# TB_Controller.net
KiCad netlist of a schematic drawn in Altium Designer
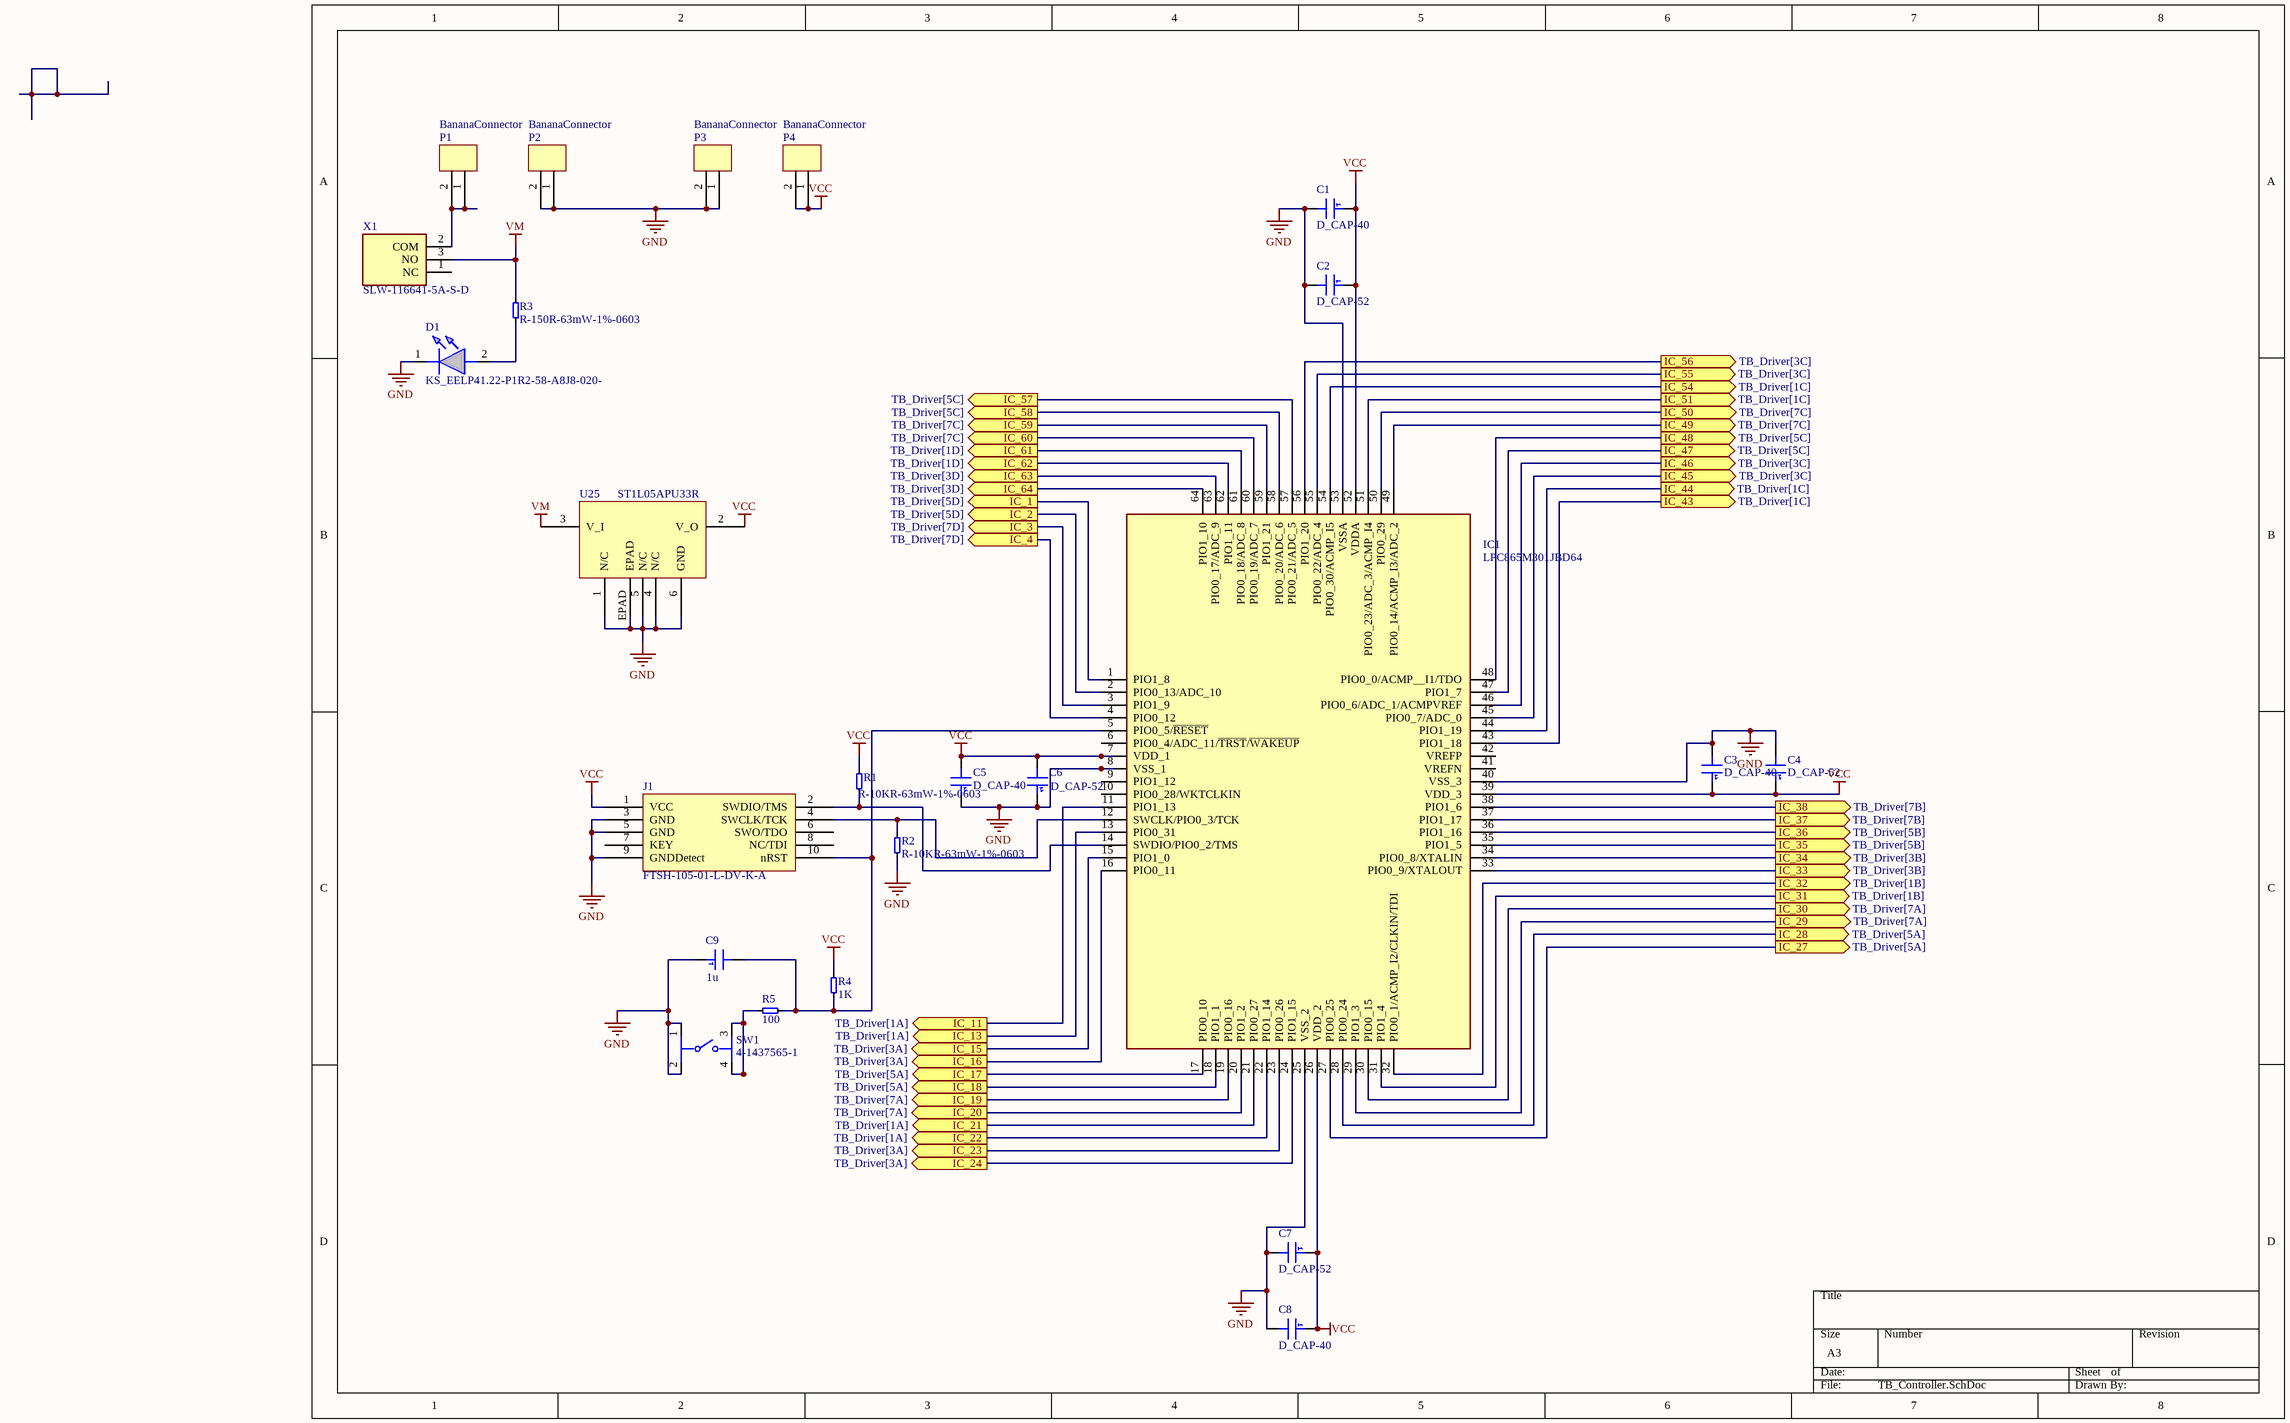
[diagram p0: TB_Controller.SchDoc]

(export (version "E")
  (design (tool "Eeschema 10.0.6"))
  (components
    (comp (ref "C1")
      (value "D_CAP-40")
      (footprint "CAP_0603H0.8")
      (description "Boite Labo 0603: Ceramic Cap, 10nF, 5%, 50V, CAP_0603H0.8")
      (fields (field (name "MANUFACTURER") "Murata") (field (name "DESIGNER") "R.Mastrocola"))
      (libsource (lib "A365 Rehosted HEPIA Vault") (part "Cap"))
    )
    (comp (ref "C2")
      (value "D_CAP-52")
      (footprint "CAP_0603H0.8")
      (description "Boite Labo 0603: Ceramic Cap, 100nF, 10%, 50V, CAP_0603H0.8")
      (fields (field (name "MANUFACTURER") "Murata") (field (name "DESIGNER") "R.Mastrocola"))
      (libsource (lib "A365 Rehosted HEPIA Vault") (part "Cap"))
    )
    (comp (ref "C3")
      (value "D_CAP-40")
      (footprint "CAP_0603H0.8")
      (description "Boite Labo 0603: Ceramic Cap, 10nF, 5%, 50V, CAP_0603H0.8")
      (fields (field (name "MANUFACTURER") "Murata") (field (name "DESIGNER") "R.Mastrocola"))
      (libsource (lib "A365 Rehosted HEPIA Vault") (part "Cap"))
    )
    (comp (ref "C4")
      (value "D_CAP-52")
      (footprint "CAP_0603H0.8")
      (description "Boite Labo 0603: Ceramic Cap, 100nF, 10%, 50V, CAP_0603H0.8")
      (fields (field (name "MANUFACTURER") "Murata") (field (name "DESIGNER") "R.Mastrocola"))
      (libsource (lib "A365 Rehosted HEPIA Vault") (part "Cap"))
    )
    (comp (ref "C5")
      (value "D_CAP-40")
      (footprint "CAP_0603H0.8")
      (description "Boite Labo 0603: Ceramic Cap, 10nF, 5%, 50V, CAP_0603H0.8")
      (fields (field (name "MANUFACTURER") "Murata") (field (name "DESIGNER") "R.Mastrocola"))
      (libsource (lib "A365 Rehosted HEPIA Vault") (part "Cap"))
    )
    (comp (ref "C6")
      (value "D_CAP-52")
      (footprint "CAP_0603H0.8")
      (description "Boite Labo 0603: Ceramic Cap, 100nF, 10%, 50V, CAP_0603H0.8")
      (fields (field (name "MANUFACTURER") "Murata") (field (name "DESIGNER") "R.Mastrocola"))
      (libsource (lib "A365 Rehosted HEPIA Vault") (part "Cap"))
    )
    (comp (ref "C7")
      (value "D_CAP-52")
      (footprint "CAP_0603H0.8")
      (description "Boite Labo 0603: Ceramic Cap, 100nF, 10%, 50V, CAP_0603H0.8")
      (fields (field (name "MANUFACTURER") "Murata") (field (name "DESIGNER") "R.Mastrocola"))
      (libsource (lib "A365 Rehosted HEPIA Vault") (part "Cap"))
    )
    (comp (ref "C8")
      (value "D_CAP-40")
      (footprint "CAP_0603H0.8")
      (description "Boite Labo 0603: Ceramic Cap, 10nF, 5%, 50V, CAP_0603H0.8")
      (fields (field (name "MANUFACTURER") "Murata") (field (name "DESIGNER") "R.Mastrocola"))
      (libsource (lib "A365 Rehosted HEPIA Vault") (part "Cap"))
    )
    (comp (ref "C9")
      (value "1u")
      (footprint "CAP_0603H0.8")
      (description "Boite Labo 0603: Ceramic Cap, 1uF, 10%, 50V, CAP_0603H0.8")
      (fields
        (field (name "PART NUMBER") "D_CAP-64")
        (field (name "MANUFACTURER") "Murata")
        (field (name "DESIGNER") "R.Mastrocola")
      )
      (libsource (lib "A365 Rehosted HEPIA Vault") (part "Cap"))
    )
    (comp (ref "D1")
      (value "KS_EELP41.22-P1R2-58-A8J8-020-")
      (footprint "KSEELP4122P1R258A8J8020R18")
      (description "Standard LEDs - SMD 0603 (1608 metric)")
      (fields
        (field (name "MOUSER PART NUMBER") "720-P412P1R258A8J802")
        (field (name "MANUFACTURER_PART_NUMBER") "KS EELP41.22-P1R2-58-A8J8-020-R18")
      )
      (libsource (lib "TB_Components") (part "KS_EELP41.22-P1R2-58-A8J8-020-"))
    )
    (comp (ref "IC1")
      (value "LPC865M301JBD64")
      (footprint "LPC865M301JBD64")
      (libsource (lib "TB_Components") (part "LPC865M301JBD64"))
    )
    (comp (ref "J1")
      (value "FTSH-105-01-L-DV-K-A")
      (footprint "FTSH-105-01-L-DV-K-A")
      (libsource (lib "TB_Components") (part "FTSH-105-01-L-DV-K-A"))
    )
    (comp (ref "P1")
      (value "BananaConnector")
      (footprint "Delton Banana Plug 500 Red")
      (libsource (lib "TB_Components") (part "BananaConnector"))
    )
    (comp (ref "P2")
      (value "BananaConnector")
      (footprint "Delton Banana Plug 100 Black")
      (libsource (lib "TB_Components") (part "BananaConnector"))
    )
    (comp (ref "P3")
      (value "BananaConnector")
      (footprint "Delton Banana Plug 100 Black")
      (libsource (lib "TB_Components") (part "BananaConnector"))
    )
    (comp (ref "P4")
      (value "BananaConnector")
      (footprint "Delton Banana Plug 500 Red")
      (libsource (lib "TB_Components") (part "BananaConnector"))
    )
    (comp (ref "R1")
      (value "R-10KR-63mW-1%-0603")
      (footprint "T_RESC0603X30N")
      (description "Resistor 10 Kohm 63mW 1% 0603")
      (fields (field (name "TOLERANCE") "1%") (field (name "SOURCE") "Ixora.SchLib"))
      (libsource (lib "A365 Rehosted HEPIA Vault") (part "R-40.2KR-63mW-1%-0603"))
    )
    (comp (ref "R2")
      (value "R-10KR-63mW-1%-0603")
      (footprint "T_RESC0603X30N")
      (description "Resistor 10 Kohm 63mW 1% 0603")
      (fields (field (name "TOLERANCE") "1%") (field (name "SOURCE") "Ixora.SchLib"))
      (libsource (lib "A365 Rehosted HEPIA Vault") (part "R-40.2KR-63mW-1%-0603"))
    )
    (comp (ref "R3")
      (value "R-150R-63mW-1%-0603")
      (footprint "T_RESC0603X30N")
      (description "Resistor 150 ohm 63mW 1% 0603")
      (fields (field (name "TOLERANCE") "1%") (field (name "SOURCE") "Ixora.SchLib"))
      (libsource (lib "A365 Rehosted HEPIA Vault") (part "R-40.2KR-63mW-1%-0603"))
    )
    (comp (ref "R4")
      (value "1K")
      (footprint "T_RESC0603X30N")
      (description "Resistor 1 Kohm 63mW 5% 0603")
      (fields (field (name "TOLERANCE") "5%") (field (name "SOURCE") "Ixora.SchLib"))
      (libsource (lib "A365 Rehosted HEPIA Vault") (part "R-6.2KR-63mW-1%-0402"))
    )
    (comp (ref "R5")
      (value "100")
      (footprint "T_RESC0603X30N")
      (description "Resistor 100 ohm 63mW 5% 0603")
      (fields (field (name "TOLERANCE") "5%") (field (name "SOURCE") "Ixora.SchLib"))
      (libsource (lib "A365 Rehosted HEPIA Vault") (part "R-6.2KR-63mW-1%-0402"))
    )
    (comp (ref "SW1")
      (value "4-1437565-1")
      (footprint "FP-4-1437565-1-MFG")
      (description "SWITCH TACTILE SPST-NO 0.05A 24V")
      (fields
        (field (name "MANUFACTURER") "TE Connectivity")
        (field (name "OCTOPART") "https://octopart.com/fsm4jsma-te+connectivity-55488004")
      )
      (libsource (lib "Altium Content Vault") (part "b8895f3f4cefb76e1819d2863dba89b"))
    )
    (comp (ref "U25")
      (value "ST1L05APU33R")
      (footprint "ST1L05APU33R")
      (description "DFN6 (3x3 mm) Input -0.3 to 7V and output 3.3V at max 1.3A")
      (libsource (lib "TB_Components") (part "ST1L05APU33R"))
    )
    (comp (ref "X1")
      (value "SLW-116641-5A-S-D")
      (footprint "SLW-116641-5A-S-D")
      (description "11.6 x 6 x 4.1 mm, 5 mm Raised Slide Actuator, Through Hole, Slide Switch")
      (libsource (lib "TB_Components") (part "SLW-116641-5A-S-D"))
    )
  )
  (nets
    (net (code "1") (name "/IC_1") (class "Default")
      (node (ref "IC1") (pin "1") (pinfunction "PIO1_8_1") (pintype "passive"))
    )
    (net (code "2") (name "/IC_2") (class "Default")
      (node (ref "IC1") (pin "2") (pinfunction "PIO0_13/ADC_10_2") (pintype "passive"))
    )
    (net (code "3") (name "/IC_3") (class "Default")
      (node (ref "IC1") (pin "3") (pinfunction "PIO1_9_3") (pintype "passive"))
    )
    (net (code "4") (name "/IC_4") (class "Default")
      (node (ref "IC1") (pin "4") (pinfunction "PIO0_12_4") (pintype "passive"))
    )
    (net (code "5") (name "/IC_11") (class "Default")
      (node (ref "IC1") (pin "11") (pinfunction "PIO1_13_11") (pintype "passive"))
    )
    (net (code "6") (name "/IC_13") (class "Default")
      (node (ref "IC1") (pin "13") (pinfunction "PIO0_31_13") (pintype "passive"))
    )
    (net (code "7") (name "/IC_15") (class "Default")
      (node (ref "IC1") (pin "15") (pinfunction "PIO1_0_15") (pintype "passive"))
    )
    (net (code "8") (name "/IC_16") (class "Default")
      (node (ref "IC1") (pin "16") (pinfunction "PIO0_11_16") (pintype "passive"))
    )
    (net (code "9") (name "/IC_17") (class "Default")
      (node (ref "IC1") (pin "17") (pinfunction "PIO0_10_17") (pintype "passive"))
    )
    (net (code "10") (name "/IC_18") (class "Default")
      (node (ref "IC1") (pin "18") (pinfunction "PIO1_1_18") (pintype "passive"))
    )
    (net (code "11") (name "/IC_19") (class "Default")
      (node (ref "IC1") (pin "19") (pinfunction "PIO0_16_19") (pintype "passive"))
    )
    (net (code "12") (name "/IC_20") (class "Default")
      (node (ref "IC1") (pin "20") (pinfunction "PIO1_2_20") (pintype "passive"))
    )
    (net (code "13") (name "/IC_21") (class "Default")
      (node (ref "IC1") (pin "21") (pinfunction "PIO0_27_21") (pintype "passive"))
    )
    (net (code "14") (name "/IC_22") (class "Default")
      (node (ref "IC1") (pin "22") (pinfunction "PIO1_14_22") (pintype "passive"))
    )
    (net (code "15") (name "/IC_23") (class "Default")
      (node (ref "IC1") (pin "23") (pinfunction "PIO0_26_23") (pintype "passive"))
    )
    (net (code "16") (name "/IC_24") (class "Default")
      (node (ref "IC1") (pin "24") (pinfunction "PIO1_15_24") (pintype "passive"))
    )
    (net (code "17") (name "/IC_27") (class "Default")
      (node (ref "IC1") (pin "27") (pinfunction "PIO0_25_27") (pintype "passive"))
    )
    (net (code "18") (name "/IC_28") (class "Default")
      (node (ref "IC1") (pin "28") (pinfunction "PIO0_24_28") (pintype "passive"))
    )
    (net (code "19") (name "/IC_29") (class "Default")
      (node (ref "IC1") (pin "29") (pinfunction "PIO1_3_29") (pintype "passive"))
    )
    (net (code "20") (name "/IC_30") (class "Default")
      (node (ref "IC1") (pin "30") (pinfunction "PIO0_15_30") (pintype "passive"))
    )
    (net (code "21") (name "/IC_31") (class "Default")
      (node (ref "IC1") (pin "31") (pinfunction "PIO1_4_31") (pintype "passive"))
    )
    (net (code "22") (name "/IC_32") (class "Default")
      (node (ref "IC1") (pin "32") (pinfunction "PIO0_1/ACMP_I2/CLKIN/TDI_32") (pintype "passive"))
    )
    (net (code "23") (name "/IC_33") (class "Default")
      (node (ref "IC1") (pin "33") (pinfunction "PIO0_9/XTALOUT_33") (pintype "passive"))
    )
    (net (code "24") (name "/IC_34") (class "Default")
      (node (ref "IC1") (pin "34") (pinfunction "PIO0_8/XTALIN_34") (pintype "passive"))
    )
    (net (code "25") (name "/IC_35") (class "Default")
      (node (ref "IC1") (pin "35") (pinfunction "PIO1_5_35") (pintype "passive"))
    )
    (net (code "26") (name "/IC_36") (class "Default")
      (node (ref "IC1") (pin "36") (pinfunction "PIO1_16_36") (pintype "passive"))
    )
    (net (code "27") (name "/IC_37") (class "Default")
      (node (ref "IC1") (pin "37") (pinfunction "PIO1_17_37") (pintype "passive"))
    )
    (net (code "28") (name "/IC_38") (class "Default")
      (node (ref "IC1") (pin "38") (pinfunction "PIO1_6_38") (pintype "passive"))
    )
    (net (code "29") (name "/IC_43") (class "Default")
      (node (ref "IC1") (pin "43") (pinfunction "PIO1_18_43") (pintype "passive"))
    )
    (net (code "30") (name "/IC_44") (class "Default")
      (node (ref "IC1") (pin "44") (pinfunction "PIO1_19_44") (pintype "passive"))
    )
    (net (code "31") (name "/IC_45") (class "Default")
      (node (ref "IC1") (pin "45") (pinfunction "PIO0_7/ADC_0_45") (pintype "passive"))
    )
    (net (code "32") (name "/IC_46") (class "Default")
      (node (ref "IC1") (pin "46") (pinfunction "PIO0_6/ADC_1/ACMPVREF_46") (pintype "passive"))
    )
    (net (code "33") (name "/IC_47") (class "Default")
      (node (ref "IC1") (pin "47") (pinfunction "PIO1_7_47") (pintype "passive"))
    )
    (net (code "34") (name "/IC_48") (class "Default")
      (node (ref "IC1") (pin "48") (pinfunction "PIO0_0/ACMP__I1/TDO_48") (pintype "passive"))
    )
    (net (code "35") (name "/IC_49") (class "Default")
      (node (ref "IC1") (pin "49") (pinfunction "PIO0_14/ACMP_I3/ADC_2_49") (pintype "passive"))
    )
    (net (code "36") (name "/IC_50") (class "Default")
      (node (ref "IC1") (pin "50") (pinfunction "PIO0_29_50") (pintype "passive"))
    )
    (net (code "37") (name "/IC_51") (class "Default")
      (node (ref "IC1") (pin "51") (pinfunction "PIO0_23/ADC_3/ACMP_I4_51") (pintype "passive"))
    )
    (net (code "38") (name "/IC_54") (class "Default")
      (node (ref "IC1") (pin "54") (pinfunction "PIO0_30/ACMP_I5_54") (pintype "passive"))
    )
    (net (code "39") (name "/IC_55") (class "Default")
      (node (ref "IC1") (pin "55") (pinfunction "PIO0_22/ADC_4_55") (pintype "passive"))
    )
    (net (code "40") (name "/IC_56") (class "Default")
      (node (ref "IC1") (pin "56") (pinfunction "PIO1_20_56") (pintype "passive"))
    )
    (net (code "41") (name "/IC_57") (class "Default")
      (node (ref "IC1") (pin "57") (pinfunction "PIO0_21/ADC_5_57") (pintype "passive"))
    )
    (net (code "42") (name "/IC_58") (class "Default")
      (node (ref "IC1") (pin "58") (pinfunction "PIO0_20/ADC_6_58") (pintype "passive"))
    )
    (net (code "43") (name "/IC_59") (class "Default")
      (node (ref "IC1") (pin "59") (pinfunction "PIO1_21_59") (pintype "passive"))
    )
    (net (code "44") (name "/IC_60") (class "Default")
      (node (ref "IC1") (pin "60") (pinfunction "PIO0_19/ADC_7_60") (pintype "passive"))
    )
    (net (code "45") (name "/IC_61") (class "Default")
      (node (ref "IC1") (pin "61") (pinfunction "PIO0_18/ADC_8_61") (pintype "passive"))
    )
    (net (code "46") (name "/IC_62") (class "Default")
      (node (ref "IC1") (pin "62") (pinfunction "PIO1_11_62") (pintype "passive"))
    )
    (net (code "47") (name "/IC_63") (class "Default")
      (node (ref "IC1") (pin "63") (pinfunction "PIO0_17/ADC_9_63") (pintype "passive"))
    )
    (net (code "48") (name "/IC_64") (class "Default")
      (node (ref "IC1") (pin "64") (pinfunction "PIO1_10_64") (pintype "passive"))
    )
    (net (code "49") (name "GND") (class "Default")
      (node (ref "C1") (pin "2") (pinfunction "2_2") (pintype "passive"))
      (node (ref "C2") (pin "2") (pinfunction "2_2") (pintype "passive"))
      (node (ref "C3") (pin "2") (pinfunction "2_2") (pintype "passive"))
      (node (ref "C4") (pin "2") (pinfunction "2_2") (pintype "passive"))
      (node (ref "C5") (pin "1") (pinfunction "1_1") (pintype "passive"))
      (node (ref "C6") (pin "1") (pinfunction "1_1") (pintype "passive"))
      (node (ref "C7") (pin "2") (pinfunction "2_2") (pintype "passive"))
      (node (ref "C8") (pin "2") (pinfunction "2_2") (pintype "passive"))
      (node (ref "C9") (pin "1") (pinfunction "1_1") (pintype "passive"))
      (node (ref "D1") (pin "1") (pinfunction "K_1") (pintype "passive"))
      (node (ref "IC1") (pin "25") (pinfunction "VSS_2_25") (pintype "passive"))
      (node (ref "IC1") (pin "40") (pinfunction "VSS_3_40") (pintype "passive"))
      (node (ref "IC1") (pin "53") (pinfunction "VSSA_53") (pintype "passive"))
      (node (ref "IC1") (pin "8") (pinfunction "VSS_1_8") (pintype "passive"))
      (node (ref "J1") (pin "3") (pinfunction "GND_3") (pintype "passive"))
      (node (ref "J1") (pin "5") (pinfunction "GND_5") (pintype "passive"))
      (node (ref "J1") (pin "9") (pinfunction "GNDDetect_9") (pintype "passive"))
      (node (ref "P2") (pin "1") (pintype "passive"))
      (node (ref "P2") (pin "2") (pintype "passive"))
      (node (ref "P3") (pin "1") (pintype "passive"))
      (node (ref "P3") (pin "2") (pintype "passive"))
      (node (ref "R2") (pin "1") (pinfunction "1_1") (pintype "passive"))
      (node (ref "SW1") (pin "1") (pinfunction "1_1") (pintype "passive"))
      (node (ref "SW1") (pin "2") (pinfunction "2_2") (pintype "passive"))
      (node (ref "U25") (pin "1") (pinfunction "N/C_1") (pintype "passive"))
      (node (ref "U25") (pin "4") (pinfunction "N/C_4") (pintype "passive"))
      (node (ref "U25") (pin "5") (pinfunction "N/C_5") (pintype "passive"))
      (node (ref "U25") (pin "6") (pinfunction "GND_6") (pintype "passive"))
      (node (ref "U25") (pin "EPAD") (pinfunction "EPAD_EPAD") (pintype "passive"))
    )
    (net (code "50") (name "Net-(D1-A)") (class "Default")
      (node (ref "D1") (pin "2") (pinfunction "A_2") (pintype "passive"))
      (node (ref "R3") (pin "1") (pinfunction "1_1") (pintype "passive"))
    )
    (net (code "51") (name "Net-(IC1-PIO0_5{slash}~{RESET})") (class "Default")
      (node (ref "C9") (pin "2") (pinfunction "2_2") (pintype "passive"))
      (node (ref "IC1") (pin "5") (pinfunction "PIO0_5/~{RESET}_5") (pintype "passive"))
      (node (ref "J1") (pin "10") (pinfunction "nRST_10") (pintype "passive"))
      (node (ref "R4") (pin "1") (pinfunction "1_1") (pintype "passive"))
      (node (ref "R5") (pin "2") (pinfunction "2_2") (pintype "passive"))
    )
    (net (code "52") (name "Net-(IC1-SWCLK{slash}PIO0_3{slash}TCK)") (class "Default")
      (node (ref "IC1") (pin "12") (pinfunction "SWCLK/PIO0_3/TCK_12") (pintype "passive"))
      (node (ref "J1") (pin "4") (pinfunction "SWCLK/TCK_4") (pintype "passive"))
      (node (ref "R2") (pin "2") (pinfunction "2_2") (pintype "passive"))
    )
    (net (code "53") (name "Net-(IC1-SWDIO{slash}PIO0_2{slash}TMS)") (class "Default")
      (node (ref "IC1") (pin "14") (pinfunction "SWDIO/PIO0_2/TMS_14") (pintype "passive"))
      (node (ref "J1") (pin "2") (pinfunction "SWDIO/TMS_2") (pintype "passive"))
      (node (ref "R1") (pin "1") (pinfunction "1_1") (pintype "passive"))
    )
    (net (code "54") (name "Net-(R5-Pad1)") (class "Default")
      (node (ref "R5") (pin "1") (pinfunction "1_1") (pintype "passive"))
      (node (ref "SW1") (pin "3") (pinfunction "3_3") (pintype "passive"))
      (node (ref "SW1") (pin "4") (pinfunction "4_4") (pintype "passive"))
    )
    (net (code "55") (name "Net-(X1-COM)") (class "Default")
      (node (ref "P1") (pin "1") (pintype "passive"))
      (node (ref "P1") (pin "2") (pintype "passive"))
      (node (ref "X1") (pin "2") (pinfunction "COM_2") (pintype "passive"))
    )
    (net (code "56") (name "VCC") (class "Default")
      (node (ref "C1") (pin "1") (pinfunction "1_1") (pintype "passive"))
      (node (ref "C2") (pin "1") (pinfunction "1_1") (pintype "passive"))
      (node (ref "C3") (pin "1") (pinfunction "1_1") (pintype "passive"))
      (node (ref "C4") (pin "1") (pinfunction "1_1") (pintype "passive"))
      (node (ref "C5") (pin "2") (pinfunction "2_2") (pintype "passive"))
      (node (ref "C6") (pin "2") (pinfunction "2_2") (pintype "passive"))
      (node (ref "C7") (pin "1") (pinfunction "1_1") (pintype "passive"))
      (node (ref "C8") (pin "1") (pinfunction "1_1") (pintype "passive"))
      (node (ref "IC1") (pin "26") (pinfunction "VDD_2_26") (pintype "passive"))
      (node (ref "IC1") (pin "39") (pinfunction "VDD_3_39") (pintype "passive"))
      (node (ref "IC1") (pin "52") (pinfunction "VDDA_52") (pintype "passive"))
      (node (ref "IC1") (pin "7") (pinfunction "VDD_1_7") (pintype "passive"))
      (node (ref "J1") (pin "1") (pinfunction "VCC_1") (pintype "passive"))
      (node (ref "P4") (pin "1") (pintype "passive"))
      (node (ref "P4") (pin "2") (pintype "passive"))
      (node (ref "R1") (pin "2") (pinfunction "2_2") (pintype "passive"))
      (node (ref "R4") (pin "2") (pinfunction "2_2") (pintype "passive"))
      (node (ref "U25") (pin "2") (pinfunction "V_O_2") (pintype "passive"))
    )
    (net (code "57") (name "VM") (class "Default")
      (node (ref "R3") (pin "2") (pinfunction "2_2") (pintype "passive"))
      (node (ref "U25") (pin "3") (pinfunction "V_I_3") (pintype "passive"))
      (node (ref "X1") (pin "3") (pinfunction "NO_3") (pintype "passive"))
    )
    (net (code "58") (name "unconnected-(IC1-PIO0_4{slash}ADC_11{slash}~{TRST}{slash}~{WAKEUP}-Pad6)") (class "Default")
      (node (ref "IC1") (pin "6") (pinfunction "PIO0_4/ADC_11/~{TRST}/~{WAKEUP}_6") (pintype "passive"))
    )
    (net (code "59") (name "unconnected-(IC1-PIO0_28{slash}WKTCLKIN-Pad10)") (class "Default")
      (node (ref "IC1") (pin "10") (pinfunction "PIO0_28/WKTCLKIN_10") (pintype "passive"))
    )
    (net (code "60") (name "unconnected-(IC1-PIO1_12-Pad9)") (class "Default")
      (node (ref "IC1") (pin "9") (pinfunction "PIO1_12_9") (pintype "passive"))
    )
    (net (code "61") (name "unconnected-(IC1-VREFN-Pad41)") (class "Default")
      (node (ref "IC1") (pin "41") (pinfunction "VREFN_41") (pintype "passive"))
    )
    (net (code "62") (name "unconnected-(IC1-VREFP-Pad42)") (class "Default")
      (node (ref "IC1") (pin "42") (pinfunction "VREFP_42") (pintype "passive"))
    )
    (net (code "63") (name "unconnected-(J1-KEY-Pad7)") (class "Default")
      (node (ref "J1") (pin "7") (pinfunction "KEY_7") (pintype "passive"))
    )
    (net (code "64") (name "unconnected-(J1-NC{slash}TDI-Pad8)") (class "Default")
      (node (ref "J1") (pin "8") (pinfunction "NC/TDI_8") (pintype "passive"))
    )
    (net (code "65") (name "unconnected-(J1-SWO{slash}TDO-Pad6)") (class "Default")
      (node (ref "J1") (pin "6") (pinfunction "SWO/TDO_6") (pintype "passive"))
    )
    (net (code "66") (name "unconnected-(X1-NC-Pad1)") (class "Default")
      (node (ref "X1") (pin "1") (pinfunction "NC_1") (pintype "passive"))
    )
  )
)
